# Timer_PCB_Project.net
KiCad netlist of a schematic drawn in EasyEDA Pro
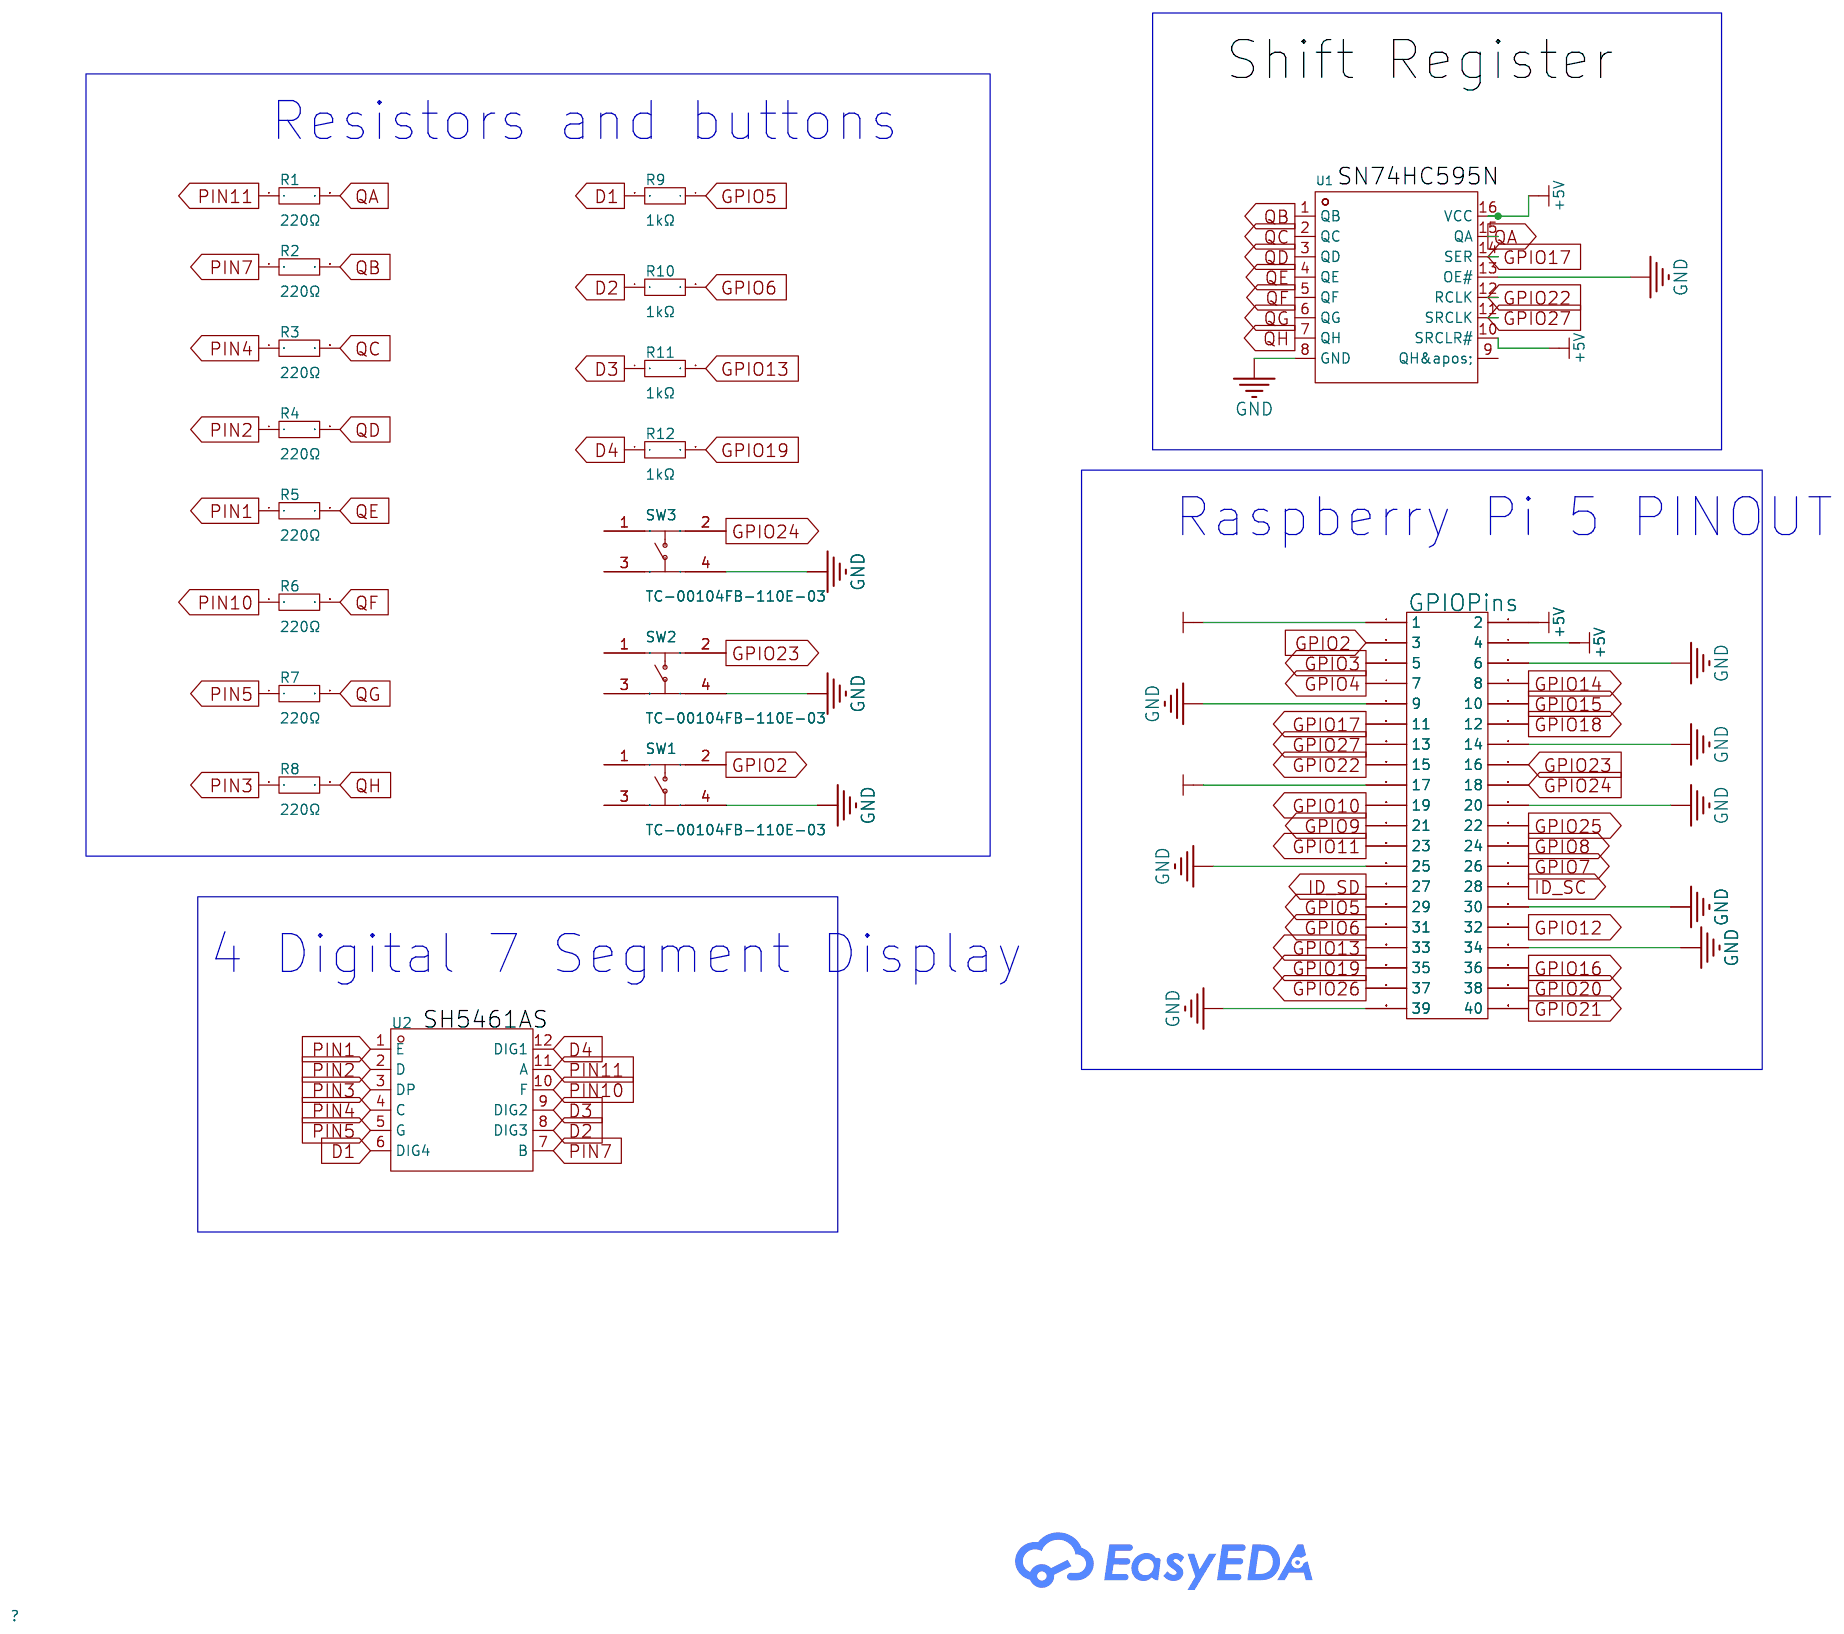
[diagram p0: schematic sheet]

(export (version "E")
  (design (tool "Eeschema 10.0.6"))
  (components
    (comp (ref "GPIOPins")
      (value "2.54间距 双排弯针")
      (footprint "easyedapro:HDR-TH_20P-P2.54-H-R2-C10-S2.54-W12.0")
      (libsource (lib "easyedapro") (part "2.54pitch header"))
    )
    (comp (ref "R1")
      (value "220Ω")
      (footprint "easyedapro:RES-TH_BD1.8-L3.2-P7.20-D0.4")
      (libsource (lib "easyedapro") (part "Res"))
    )
    (comp (ref "R2")
      (value "220Ω")
      (footprint "easyedapro:RES-TH_BD1.8-L3.2-P7.20-D0.4")
      (libsource (lib "easyedapro") (part "Res"))
    )
    (comp (ref "R3")
      (value "220Ω")
      (footprint "easyedapro:RES-TH_BD1.8-L3.2-P7.20-D0.4")
      (libsource (lib "easyedapro") (part "Res"))
    )
    (comp (ref "R4")
      (value "220Ω")
      (footprint "easyedapro:RES-TH_BD1.8-L3.2-P7.20-D0.4")
      (libsource (lib "easyedapro") (part "Res"))
    )
    (comp (ref "R5")
      (value "220Ω")
      (footprint "easyedapro:RES-TH_BD1.8-L3.2-P7.20-D0.4")
      (libsource (lib "easyedapro") (part "Res"))
    )
    (comp (ref "R6")
      (value "220Ω")
      (footprint "easyedapro:RES-TH_BD1.8-L3.2-P7.20-D0.4")
      (libsource (lib "easyedapro") (part "Res"))
    )
    (comp (ref "R7")
      (value "220Ω")
      (footprint "easyedapro:RES-TH_BD1.8-L3.2-P7.20-D0.4")
      (libsource (lib "easyedapro") (part "Res"))
    )
    (comp (ref "R8")
      (value "220Ω")
      (footprint "easyedapro:RES-TH_BD1.8-L3.2-P7.20-D0.4")
      (libsource (lib "easyedapro") (part "Res"))
    )
    (comp (ref "R9")
      (value "1kΩ")
      (footprint "easyedapro:RES-TH_BD1.8-L3.2-P7.20-D0.4")
      (libsource (lib "easyedapro") (part "Res"))
    )
    (comp (ref "R10")
      (value "1kΩ")
      (footprint "easyedapro:RES-TH_BD1.8-L3.2-P7.20-D0.4")
      (libsource (lib "easyedapro") (part "Res"))
    )
    (comp (ref "R11")
      (value "1kΩ")
      (footprint "easyedapro:RES-TH_BD1.8-L3.2-P7.20-D0.4")
      (libsource (lib "easyedapro") (part "Res"))
    )
    (comp (ref "R12")
      (value "1kΩ")
      (footprint "easyedapro:RES-TH_BD1.8-L3.2-P7.20-D0.4")
      (libsource (lib "easyedapro") (part "Res"))
    )
    (comp (ref "SW1")
      (value "TC-00104FB-110E-03")
      (footprint "easyedapro:SW-TH_4P-L6.0-W6.0-P4.50-LS6.5")
      (description "Contact Current:50mA Voltage Rating (DC):12V")
      (fields (field (name "Manufacturer") "HOOYA(皓宇电子)"))
      (libsource (lib "easyedapro") (part "TC-00104FB-110E-03"))
    )
    (comp (ref "SW2")
      (value "TC-00104FB-110E-03")
      (footprint "easyedapro:SW-TH_4P-L6.0-W6.0-P4.50-LS6.5")
      (description "Contact Current:50mA Voltage Rating (DC):12V")
      (fields (field (name "Manufacturer") "HOOYA(皓宇电子)"))
      (libsource (lib "easyedapro") (part "TC-00104FB-110E-03"))
    )
    (comp (ref "SW3")
      (value "TC-00104FB-110E-03")
      (footprint "easyedapro:SW-TH_4P-L6.0-W6.0-P4.50-LS6.5")
      (description "Contact Current:50mA Voltage Rating (DC):12V")
      (fields (field (name "Manufacturer") "HOOYA(皓宇电子)"))
      (libsource (lib "easyedapro") (part "TC-00104FB-110E-03"))
    )
    (comp (ref "U1")
      (value "SN74HC595N")
      (footprint "easyedapro:DIP-16_L19.8-W6.5-P2.54-LS7.6-BL")
      (fields (field (name "Manufacturer") "TI(德州仪器)"))
      (libsource (lib "easyedapro") (part "SN74HC595N"))
    )
    (comp (ref "U2")
      (value "SH5461AS")
      (footprint "easyedapro:LED-SEG-TH_12P-L24.0-W10.0-P2.54-S7.60")
      (libsource (lib "easyedapro") (part "KYX-2453AS"))
    )
  )
  (nets
    (net (code "1") (name "+3.3V") (class "Default")
      (node (ref "GPIOPins") (pin "1") (pinfunction "1_1") (pintype "input"))
      (node (ref "GPIOPins") (pin "17") (pinfunction "17_17") (pintype "input"))
    )
    (net (code "2") (name "+5V") (class "Default")
      (node (ref "GPIOPins") (pin "2") (pinfunction "2_2") (pintype "input"))
      (node (ref "GPIOPins") (pin "4") (pinfunction "4_4") (pintype "input"))
      (node (ref "U1") (pin "10") (pinfunction "SRCLR#_10") (pintype "input"))
      (node (ref "U1") (pin "16") (pinfunction "VCC_16") (pintype "input"))
    )
    (net (code "3") (name "D1") (class "Default")
      (node (ref "R9") (pin "2") (pinfunction "2_2") (pintype "input"))
      (node (ref "U2") (pin "6") (pinfunction "DIG4_6") (pintype "unspecified"))
    )
    (net (code "4") (name "D2") (class "Default")
      (node (ref "R10") (pin "1") (pinfunction "1_1") (pintype "input"))
      (node (ref "U2") (pin "8") (pinfunction "DIG3_8") (pintype "unspecified"))
    )
    (net (code "5") (name "D3") (class "Default")
      (node (ref "R11") (pin "1") (pinfunction "1_1") (pintype "input"))
      (node (ref "U2") (pin "9") (pinfunction "DIG2_9") (pintype "unspecified"))
    )
    (net (code "6") (name "D4") (class "Default")
      (node (ref "R12") (pin "1") (pinfunction "1_1") (pintype "input"))
      (node (ref "U2") (pin "12") (pinfunction "DIG1_12") (pintype "unspecified"))
    )
    (net (code "7") (name "GND") (class "Default")
      (node (ref "GPIOPins") (pin "14") (pinfunction "14_14") (pintype "input"))
      (node (ref "GPIOPins") (pin "20") (pinfunction "20_20") (pintype "input"))
      (node (ref "GPIOPins") (pin "25") (pinfunction "25_25") (pintype "input"))
      (node (ref "GPIOPins") (pin "30") (pinfunction "30_30") (pintype "input"))
      (node (ref "GPIOPins") (pin "34") (pinfunction "34_34") (pintype "input"))
      (node (ref "GPIOPins") (pin "39") (pinfunction "39_39") (pintype "input"))
      (node (ref "GPIOPins") (pin "6") (pinfunction "6_6") (pintype "input"))
      (node (ref "GPIOPins") (pin "9") (pinfunction "9_9") (pintype "input"))
      (node (ref "SW1") (pin "4") (pinfunction "4_4") (pintype "unspecified"))
      (node (ref "SW2") (pin "4") (pinfunction "4_4") (pintype "unspecified"))
      (node (ref "SW3") (pin "4") (pinfunction "4_4") (pintype "unspecified"))
      (node (ref "U1") (pin "13") (pinfunction "OE#_13") (pintype "input"))
      (node (ref "U1") (pin "8") (pinfunction "GND_8") (pintype "input"))
    )
    (net (code "8") (name "GPIO2") (class "Default")
      (node (ref "GPIOPins") (pin "3") (pinfunction "3_3") (pintype "input"))
      (node (ref "SW1") (pin "2") (pinfunction "2_2") (pintype "unspecified"))
    )
    (net (code "9") (name "GPIO3") (class "Default")
      (node (ref "GPIOPins") (pin "5") (pinfunction "5_5") (pintype "input"))
    )
    (net (code "10") (name "GPIO4") (class "Default")
      (node (ref "GPIOPins") (pin "7") (pinfunction "7_7") (pintype "input"))
    )
    (net (code "11") (name "GPIO5") (class "Default")
      (node (ref "GPIOPins") (pin "29") (pinfunction "29_29") (pintype "input"))
      (node (ref "R9") (pin "1") (pinfunction "1_1") (pintype "input"))
    )
    (net (code "12") (name "GPIO6") (class "Default")
      (node (ref "GPIOPins") (pin "31") (pinfunction "31_31") (pintype "input"))
      (node (ref "R10") (pin "2") (pinfunction "2_2") (pintype "input"))
    )
    (net (code "13") (name "GPIO7") (class "Default")
      (node (ref "GPIOPins") (pin "26") (pinfunction "26_26") (pintype "input"))
    )
    (net (code "14") (name "GPIO8") (class "Default")
      (node (ref "GPIOPins") (pin "24") (pinfunction "24_24") (pintype "input"))
    )
    (net (code "15") (name "GPIO9") (class "Default")
      (node (ref "GPIOPins") (pin "21") (pinfunction "21_21") (pintype "input"))
    )
    (net (code "16") (name "GPIO10") (class "Default")
      (node (ref "GPIOPins") (pin "19") (pinfunction "19_19") (pintype "input"))
    )
    (net (code "17") (name "GPIO11") (class "Default")
      (node (ref "GPIOPins") (pin "23") (pinfunction "23_23") (pintype "input"))
    )
    (net (code "18") (name "GPIO12") (class "Default")
      (node (ref "GPIOPins") (pin "32") (pinfunction "32_32") (pintype "input"))
    )
    (net (code "19") (name "GPIO13") (class "Default")
      (node (ref "GPIOPins") (pin "33") (pinfunction "33_33") (pintype "input"))
      (node (ref "R11") (pin "2") (pinfunction "2_2") (pintype "input"))
    )
    (net (code "20") (name "GPIO14") (class "Default")
      (node (ref "GPIOPins") (pin "8") (pinfunction "8_8") (pintype "input"))
    )
    (net (code "21") (name "GPIO15") (class "Default")
      (node (ref "GPIOPins") (pin "10") (pinfunction "10_10") (pintype "input"))
    )
    (net (code "22") (name "GPIO16") (class "Default")
      (node (ref "GPIOPins") (pin "36") (pinfunction "36_36") (pintype "input"))
    )
    (net (code "23") (name "GPIO17") (class "Default")
      (node (ref "GPIOPins") (pin "11") (pinfunction "11_11") (pintype "input"))
      (node (ref "U1") (pin "14") (pinfunction "SER_14") (pintype "input"))
    )
    (net (code "24") (name "GPIO18") (class "Default")
      (node (ref "GPIOPins") (pin "12") (pinfunction "12_12") (pintype "input"))
    )
    (net (code "25") (name "GPIO19") (class "Default")
      (node (ref "GPIOPins") (pin "35") (pinfunction "35_35") (pintype "input"))
      (node (ref "R12") (pin "2") (pinfunction "2_2") (pintype "input"))
    )
    (net (code "26") (name "GPIO20") (class "Default")
      (node (ref "GPIOPins") (pin "38") (pinfunction "38_38") (pintype "input"))
    )
    (net (code "27") (name "GPIO21") (class "Default")
      (node (ref "GPIOPins") (pin "40") (pinfunction "40_40") (pintype "input"))
    )
    (net (code "28") (name "GPIO22") (class "Default")
      (node (ref "GPIOPins") (pin "15") (pinfunction "15_15") (pintype "input"))
      (node (ref "U1") (pin "12") (pinfunction "RCLK_12") (pintype "input"))
    )
    (net (code "29") (name "GPIO23") (class "Default")
      (node (ref "GPIOPins") (pin "16") (pinfunction "16_16") (pintype "input"))
      (node (ref "SW2") (pin "2") (pinfunction "2_2") (pintype "unspecified"))
    )
    (net (code "30") (name "GPIO24") (class "Default")
      (node (ref "GPIOPins") (pin "18") (pinfunction "18_18") (pintype "input"))
      (node (ref "SW3") (pin "2") (pinfunction "2_2") (pintype "unspecified"))
    )
    (net (code "31") (name "GPIO25") (class "Default")
      (node (ref "GPIOPins") (pin "22") (pinfunction "22_22") (pintype "input"))
    )
    (net (code "32") (name "GPIO26") (class "Default")
      (node (ref "GPIOPins") (pin "37") (pinfunction "37_37") (pintype "input"))
    )
    (net (code "33") (name "GPIO27") (class "Default")
      (node (ref "GPIOPins") (pin "13") (pinfunction "13_13") (pintype "input"))
      (node (ref "U1") (pin "11") (pinfunction "SRCLK_11") (pintype "input"))
    )
    (net (code "34") (name "ID_SC") (class "Default")
      (node (ref "GPIOPins") (pin "28") (pinfunction "28_28") (pintype "input"))
    )
    (net (code "35") (name "ID_SD") (class "Default")
      (node (ref "GPIOPins") (pin "27") (pinfunction "27_27") (pintype "input"))
    )
    (net (code "36") (name "PIN1") (class "Default")
      (node (ref "R5") (pin "1") (pinfunction "1_1") (pintype "input"))
      (node (ref "U2") (pin "1") (pinfunction "E_1") (pintype "unspecified"))
    )
    (net (code "37") (name "PIN2") (class "Default")
      (node (ref "R4") (pin "1") (pinfunction "1_1") (pintype "input"))
      (node (ref "U2") (pin "2") (pinfunction "D_2") (pintype "unspecified"))
    )
    (net (code "38") (name "PIN3") (class "Default")
      (node (ref "R8") (pin "1") (pinfunction "1_1") (pintype "input"))
      (node (ref "U2") (pin "3") (pinfunction "DP_3") (pintype "unspecified"))
    )
    (net (code "39") (name "PIN4") (class "Default")
      (node (ref "R3") (pin "1") (pinfunction "1_1") (pintype "input"))
      (node (ref "U2") (pin "4") (pinfunction "C_4") (pintype "unspecified"))
    )
    (net (code "40") (name "PIN5") (class "Default")
      (node (ref "R7") (pin "1") (pinfunction "1_1") (pintype "input"))
      (node (ref "U2") (pin "5") (pinfunction "G_5") (pintype "unspecified"))
    )
    (net (code "41") (name "PIN7") (class "Default")
      (node (ref "R2") (pin "1") (pinfunction "1_1") (pintype "input"))
      (node (ref "U2") (pin "7") (pinfunction "B_7") (pintype "unspecified"))
    )
    (net (code "42") (name "PIN10") (class "Default")
      (node (ref "R6") (pin "1") (pinfunction "1_1") (pintype "input"))
      (node (ref "U2") (pin "10") (pinfunction "F_10") (pintype "unspecified"))
    )
    (net (code "43") (name "PIN11") (class "Default")
      (node (ref "R1") (pin "1") (pinfunction "1_1") (pintype "input"))
      (node (ref "U2") (pin "11") (pinfunction "A_11") (pintype "unspecified"))
    )
    (net (code "44") (name "QA") (class "Default")
      (node (ref "R1") (pin "2") (pinfunction "2_2") (pintype "input"))
      (node (ref "U1") (pin "15") (pinfunction "QA_15") (pintype "input"))
    )
    (net (code "45") (name "QB") (class "Default")
      (node (ref "R2") (pin "2") (pinfunction "2_2") (pintype "input"))
      (node (ref "U1") (pin "1") (pinfunction "QB_1") (pintype "input"))
    )
    (net (code "46") (name "QC") (class "Default")
      (node (ref "R3") (pin "2") (pinfunction "2_2") (pintype "input"))
      (node (ref "U1") (pin "2") (pinfunction "QC_2") (pintype "input"))
    )
    (net (code "47") (name "QD") (class "Default")
      (node (ref "R4") (pin "2") (pinfunction "2_2") (pintype "input"))
      (node (ref "U1") (pin "3") (pinfunction "QD_3") (pintype "input"))
    )
    (net (code "48") (name "QE") (class "Default")
      (node (ref "R5") (pin "2") (pinfunction "2_2") (pintype "input"))
      (node (ref "U1") (pin "4") (pinfunction "QE_4") (pintype "input"))
    )
    (net (code "49") (name "QF") (class "Default")
      (node (ref "R6") (pin "2") (pinfunction "2_2") (pintype "input"))
      (node (ref "U1") (pin "5") (pinfunction "QF_5") (pintype "input"))
    )
    (net (code "50") (name "QG") (class "Default")
      (node (ref "R7") (pin "2") (pinfunction "2_2") (pintype "input"))
      (node (ref "U1") (pin "6") (pinfunction "QG_6") (pintype "input"))
    )
    (net (code "51") (name "QH") (class "Default")
      (node (ref "R8") (pin "2") (pinfunction "2_2") (pintype "input"))
      (node (ref "U1") (pin "7") (pinfunction "QH_7") (pintype "input"))
    )
    (net (code "52") (name "unconnected-(SW1-Pad1)") (class "Default")
      (node (ref "SW1") (pin "1") (pinfunction "1_1") (pintype "unspecified"))
    )
    (net (code "53") (name "unconnected-(SW1-Pad3)") (class "Default")
      (node (ref "SW1") (pin "3") (pinfunction "3_3") (pintype "unspecified"))
    )
    (net (code "54") (name "unconnected-(SW2-Pad1)") (class "Default")
      (node (ref "SW2") (pin "1") (pinfunction "1_1") (pintype "unspecified"))
    )
    (net (code "55") (name "unconnected-(SW2-Pad3)") (class "Default")
      (node (ref "SW2") (pin "3") (pinfunction "3_3") (pintype "unspecified"))
    )
    (net (code "56") (name "unconnected-(SW3-Pad1)") (class "Default")
      (node (ref "SW3") (pin "1") (pinfunction "1_1") (pintype "unspecified"))
    )
    (net (code "57") (name "unconnected-(SW3-Pad3)") (class "Default")
      (node (ref "SW3") (pin "3") (pinfunction "3_3") (pintype "unspecified"))
    )
    (net (code "58") (name "unconnected-(U1-QH&apos;-Pad9)") (class "Default")
      (node (ref "U1") (pin "9") (pinfunction "QH&apos;_9") (pintype "input"))
    )
  )
)
